# sensorX.net
KiCad netlist of a schematic drawn in EAGLE
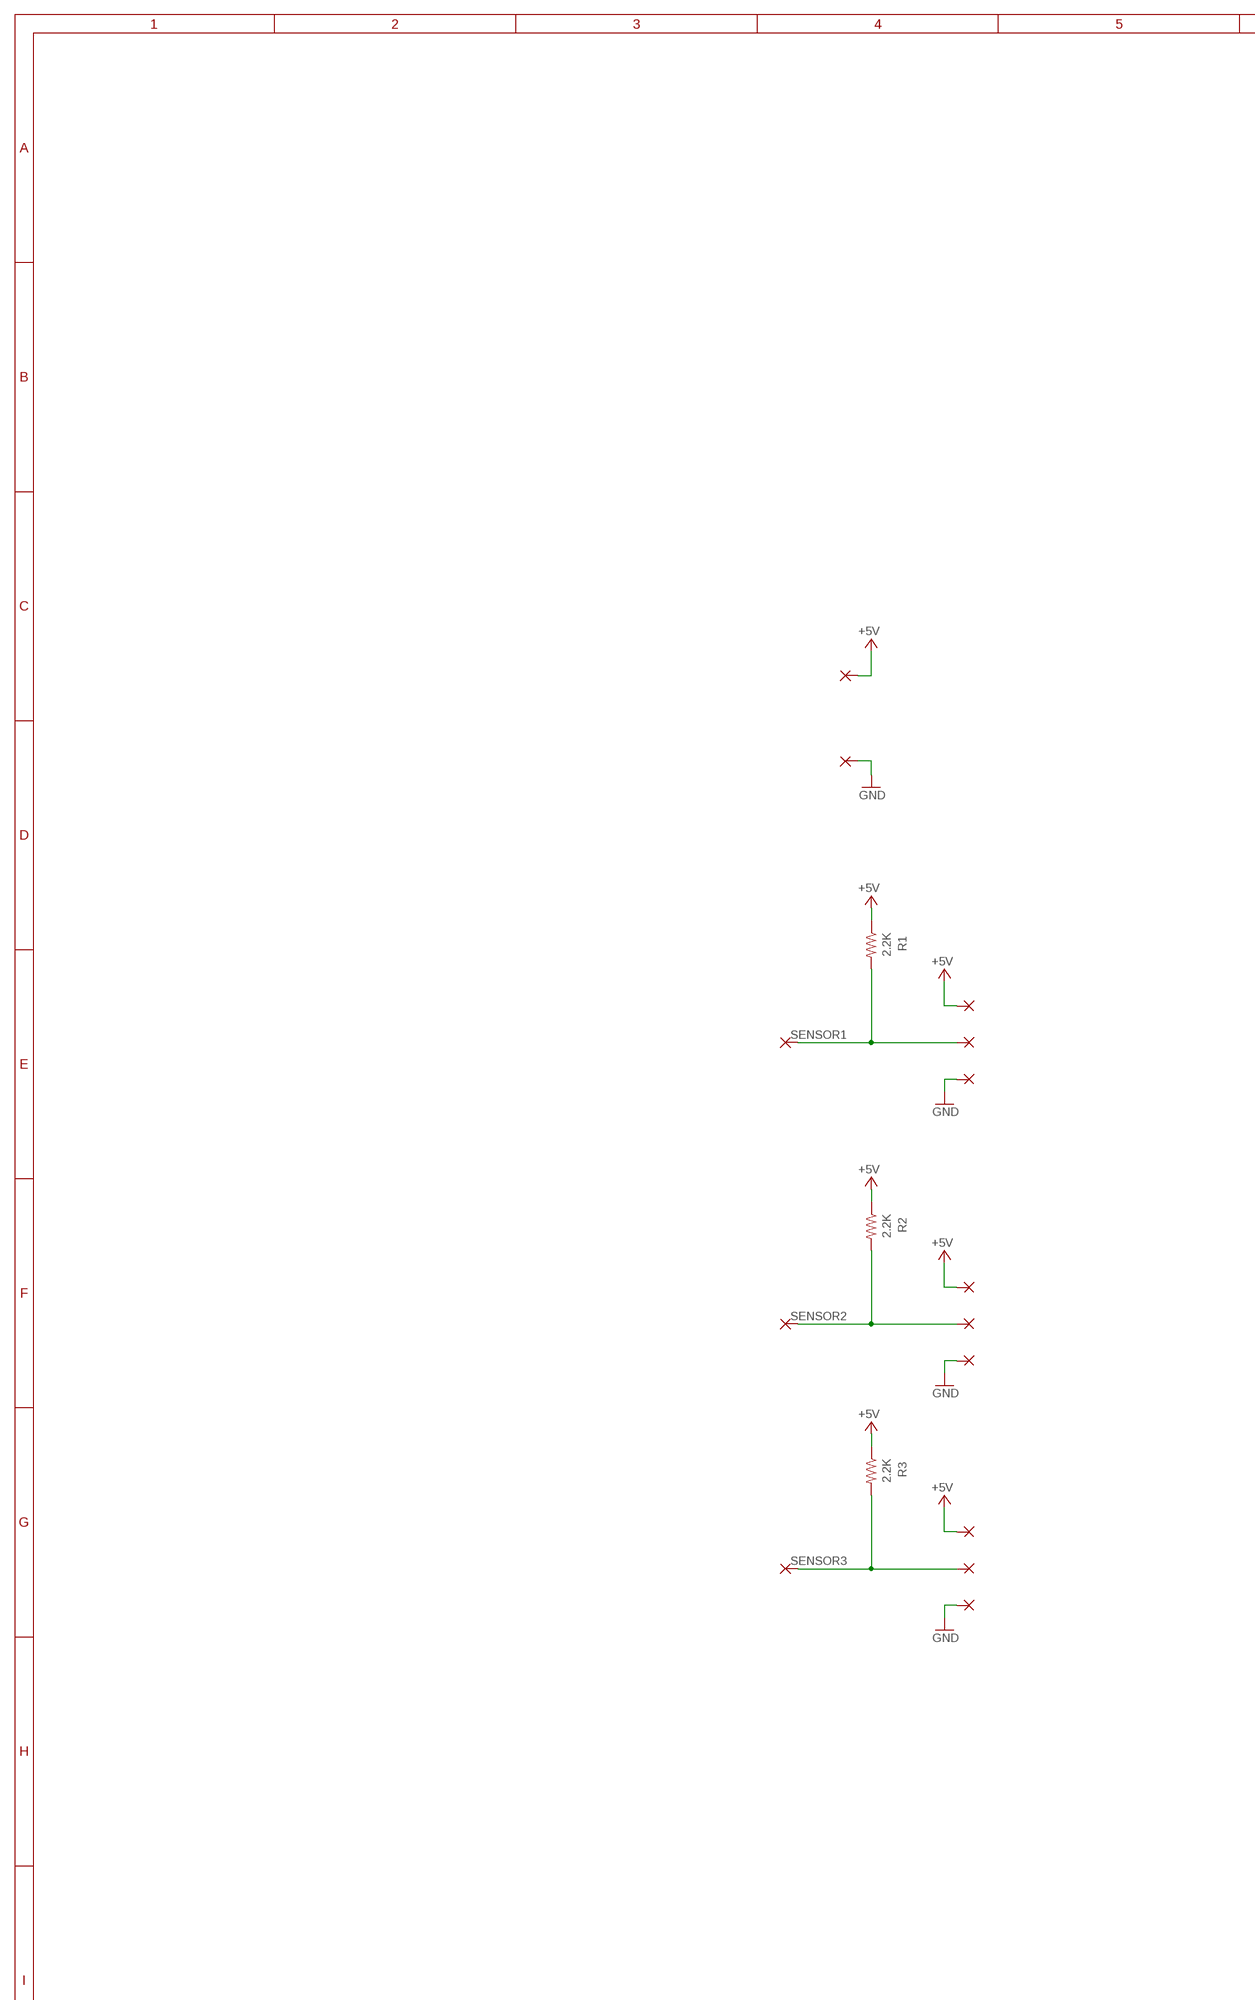
[diagram p0: schematic, sheet 1, part 1 of 2]
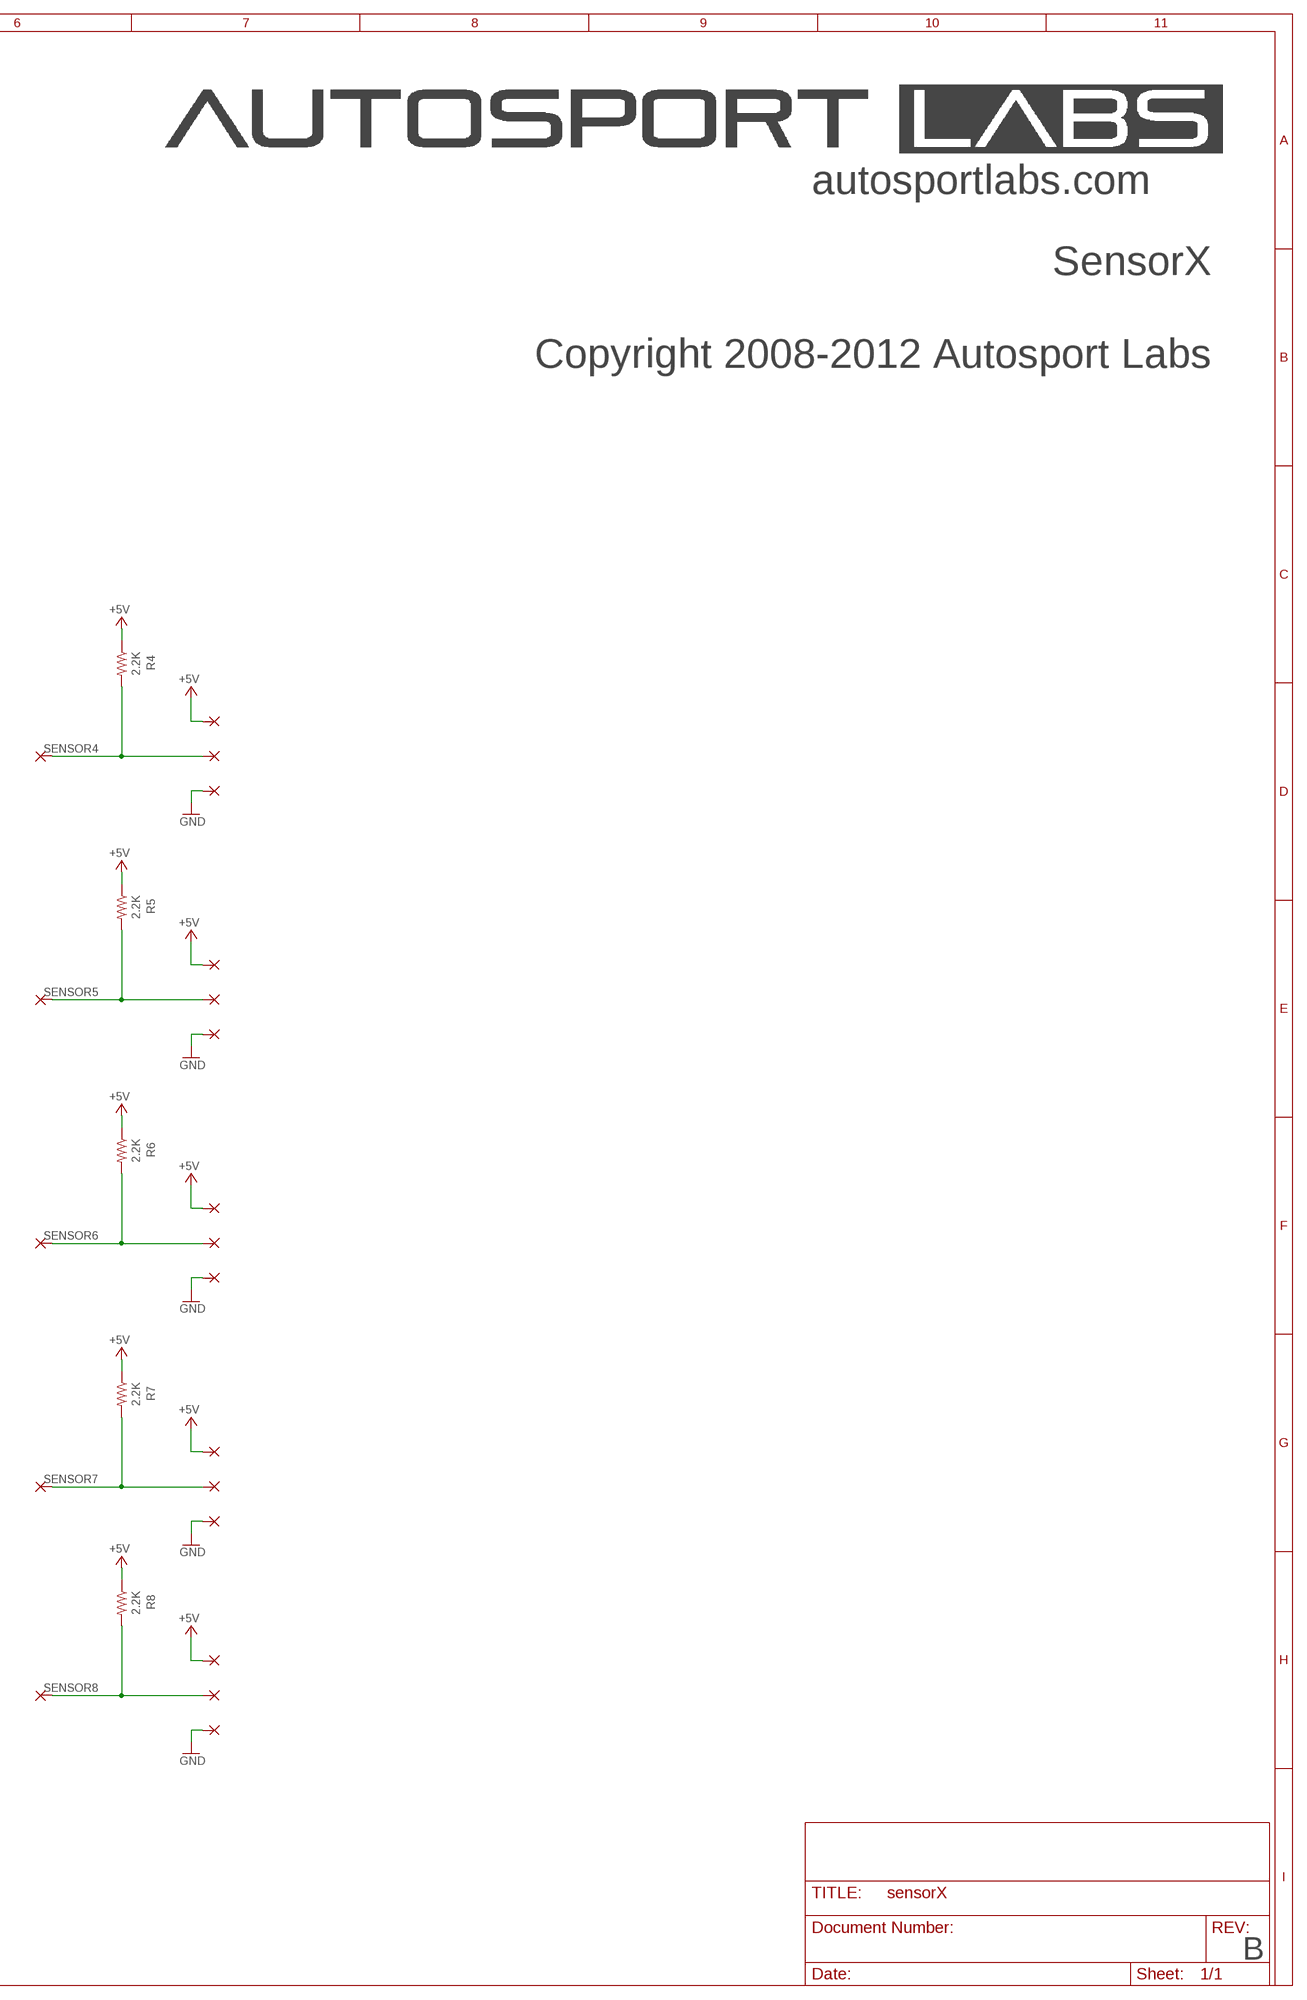
[diagram p1: schematic, sheet 1, part 2 of 2]

(export (version "E")
  (design (tool "Eeschema 10.0.6"))
  (components
    (comp (ref "1")
      (value "WIREPAD3,17/1,2")
      (footprint "eagle-import:3,17_1,2")
      (libsource (lib "eagle-import") (part "WIREPAD3,17/1,2"))
    )
    (comp (ref "2")
      (value "WIREPAD3,17/1,2")
      (footprint "eagle-import:3,17_1,2")
      (libsource (lib "eagle-import") (part "WIREPAD3,17/1,2"))
    )
    (comp (ref "3")
      (value "WIREPAD3,17/1,2")
      (footprint "eagle-import:3,17_1,2")
      (libsource (lib "eagle-import") (part "WIREPAD3,17/1,2"))
    )
    (comp (ref "4")
      (value "WIREPAD3,17/1,2")
      (footprint "eagle-import:3,17_1,2")
      (libsource (lib "eagle-import") (part "WIREPAD3,17/1,2"))
    )
    (comp (ref "5")
      (value "WIREPAD3,17/1,2")
      (footprint "eagle-import:3,17_1,2")
      (libsource (lib "eagle-import") (part "WIREPAD3,17/1,2"))
    )
    (comp (ref "5V")
      (value "WIREPAD3,17/1,2")
      (footprint "eagle-import:3,17_1,2")
      (libsource (lib "eagle-import") (part "WIREPAD3,17/1,2"))
    )
    (comp (ref "5V_1")
      (value "WIREPAD3,17/1,2")
      (footprint "eagle-import:3,17_1,2")
      (libsource (lib "eagle-import") (part "WIREPAD3,17/1,2"))
    )
    (comp (ref "5V_2")
      (value "WIREPAD3,17/1,2")
      (footprint "eagle-import:3,17_1,2")
      (libsource (lib "eagle-import") (part "WIREPAD3,17/1,2"))
    )
    (comp (ref "5V_3")
      (value "WIREPAD3,17/1,2")
      (footprint "eagle-import:3,17_1,2")
      (libsource (lib "eagle-import") (part "WIREPAD3,17/1,2"))
    )
    (comp (ref "5V_4")
      (value "WIREPAD3,17/1,2")
      (footprint "eagle-import:3,17_1,2")
      (libsource (lib "eagle-import") (part "WIREPAD3,17/1,2"))
    )
    (comp (ref "5V_5")
      (value "WIREPAD3,17/1,2")
      (footprint "eagle-import:3,17_1,2")
      (libsource (lib "eagle-import") (part "WIREPAD3,17/1,2"))
    )
    (comp (ref "5V_6")
      (value "WIREPAD3,17/1,2")
      (footprint "eagle-import:3,17_1,2")
      (libsource (lib "eagle-import") (part "WIREPAD3,17/1,2"))
    )
    (comp (ref "5V_7")
      (value "WIREPAD3,17/1,2")
      (footprint "eagle-import:3,17_1,2")
      (libsource (lib "eagle-import") (part "WIREPAD3,17/1,2"))
    )
    (comp (ref "5V_8")
      (value "WIREPAD3,17/1,2")
      (footprint "eagle-import:3,17_1,2")
      (libsource (lib "eagle-import") (part "WIREPAD3,17/1,2"))
    )
    (comp (ref "6")
      (value "WIREPAD3,17/1,2")
      (footprint "eagle-import:3,17_1,2")
      (libsource (lib "eagle-import") (part "WIREPAD3,17/1,2"))
    )
    (comp (ref "7")
      (value "WIREPAD3,17/1,2")
      (footprint "eagle-import:3,17_1,2")
      (libsource (lib "eagle-import") (part "WIREPAD3,17/1,2"))
    )
    (comp (ref "7_IN")
      (value "WIREPAD3,17/1,2")
      (footprint "eagle-import:3,17_1,2")
      (libsource (lib "eagle-import") (part "WIREPAD3,17/1,2"))
    )
    (comp (ref "8")
      (value "WIREPAD3,17/1,2")
      (footprint "eagle-import:3,17_1,2")
      (libsource (lib "eagle-import") (part "WIREPAD3,17/1,2"))
    )
    (comp (ref "8_IN")
      (value "WIREPAD3,17/1,2")
      (footprint "eagle-import:3,17_1,2")
      (libsource (lib "eagle-import") (part "WIREPAD3,17/1,2"))
    )
    (comp (ref "GND")
      (value "WIREPAD3,17/1,2")
      (footprint "eagle-import:3,17_1,2")
      (libsource (lib "eagle-import") (part "WIREPAD3,17/1,2"))
    )
    (comp (ref "GND-1")
      (value "WIREPAD3,17/1,2")
      (footprint "eagle-import:3,17_1,2")
      (libsource (lib "eagle-import") (part "WIREPAD3,17/1,2"))
    )
    (comp (ref "GND_2")
      (value "WIREPAD3,17/1,2")
      (footprint "eagle-import:3,17_1,2")
      (libsource (lib "eagle-import") (part "WIREPAD3,17/1,2"))
    )
    (comp (ref "GND_3")
      (value "WIREPAD3,17/1,2")
      (footprint "eagle-import:3,17_1,2")
      (libsource (lib "eagle-import") (part "WIREPAD3,17/1,2"))
    )
    (comp (ref "GND_4")
      (value "WIREPAD3,17/1,2")
      (footprint "eagle-import:3,17_1,2")
      (libsource (lib "eagle-import") (part "WIREPAD3,17/1,2"))
    )
    (comp (ref "GND_5")
      (value "WIREPAD3,17/1,2")
      (footprint "eagle-import:3,17_1,2")
      (libsource (lib "eagle-import") (part "WIREPAD3,17/1,2"))
    )
    (comp (ref "GND_6")
      (value "WIREPAD3,17/1,2")
      (footprint "eagle-import:3,17_1,2")
      (libsource (lib "eagle-import") (part "WIREPAD3,17/1,2"))
    )
    (comp (ref "GND_7")
      (value "WIREPAD3,17/1,2")
      (footprint "eagle-import:3,17_1,2")
      (libsource (lib "eagle-import") (part "WIREPAD3,17/1,2"))
    )
    (comp (ref "GND_8")
      (value "WIREPAD3,17/1,2")
      (footprint "eagle-import:3,17_1,2")
      (libsource (lib "eagle-import") (part "WIREPAD3,17/1,2"))
    )
    (comp (ref "IN_1")
      (value "WIREPAD3,17/1,2")
      (footprint "eagle-import:3,17_1,2")
      (libsource (lib "eagle-import") (part "WIREPAD3,17/1,2"))
    )
    (comp (ref "IN_2")
      (value "WIREPAD3,17/1,2")
      (footprint "eagle-import:3,17_1,2")
      (libsource (lib "eagle-import") (part "WIREPAD3,17/1,2"))
    )
    (comp (ref "IN_3")
      (value "WIREPAD3,17/1,2")
      (footprint "eagle-import:3,17_1,2")
      (libsource (lib "eagle-import") (part "WIREPAD3,17/1,2"))
    )
    (comp (ref "IN_4")
      (value "WIREPAD3,17/1,2")
      (footprint "eagle-import:3,17_1,2")
      (libsource (lib "eagle-import") (part "WIREPAD3,17/1,2"))
    )
    (comp (ref "IN_5")
      (value "WIREPAD3,17/1,2")
      (footprint "eagle-import:3,17_1,2")
      (libsource (lib "eagle-import") (part "WIREPAD3,17/1,2"))
    )
    (comp (ref "IN_6")
      (value "WIREPAD3,17/1,2")
      (footprint "eagle-import:3,17_1,2")
      (libsource (lib "eagle-import") (part "WIREPAD3,17/1,2"))
    )
    (comp (ref "R1")
      (value "2.2K")
      (footprint "eagle-import:0204_5")
      (libsource (lib "eagle-import") (part "R-US_0204/5"))
    )
    (comp (ref "R2")
      (value "2.2K")
      (footprint "eagle-import:0204_5")
      (libsource (lib "eagle-import") (part "R-US_0204/5"))
    )
    (comp (ref "R3")
      (value "2.2K")
      (footprint "eagle-import:0204_5")
      (libsource (lib "eagle-import") (part "R-US_0204/5"))
    )
    (comp (ref "R4")
      (value "2.2K")
      (footprint "eagle-import:0204_5")
      (libsource (lib "eagle-import") (part "R-US_0204/5"))
    )
    (comp (ref "R5")
      (value "2.2K")
      (footprint "eagle-import:0204_5")
      (libsource (lib "eagle-import") (part "R-US_0204/5"))
    )
    (comp (ref "R6")
      (value "2.2K")
      (footprint "eagle-import:0204_5")
      (libsource (lib "eagle-import") (part "R-US_0204/5"))
    )
    (comp (ref "R7")
      (value "2.2K")
      (footprint "eagle-import:0204_5")
      (libsource (lib "eagle-import") (part "R-US_0204/5"))
    )
    (comp (ref "R8")
      (value "2.2K")
      (footprint "eagle-import:0204_5")
      (libsource (lib "eagle-import") (part "R-US_0204/5"))
    )
  )
  (nets
    (net (code "1") (name "+5V") (class "Default")
      (node (ref "5V") (pin "1") (pinfunction "P_1") (pintype "passive"))
      (node (ref "5V_1") (pin "1") (pinfunction "P_1") (pintype "passive"))
      (node (ref "5V_2") (pin "1") (pinfunction "P_1") (pintype "passive"))
      (node (ref "5V_3") (pin "1") (pinfunction "P_1") (pintype "passive"))
      (node (ref "5V_4") (pin "1") (pinfunction "P_1") (pintype "passive"))
      (node (ref "5V_5") (pin "1") (pinfunction "P_1") (pintype "passive"))
      (node (ref "5V_6") (pin "1") (pinfunction "P_1") (pintype "passive"))
      (node (ref "5V_7") (pin "1") (pinfunction "P_1") (pintype "passive"))
      (node (ref "5V_8") (pin "1") (pinfunction "P_1") (pintype "passive"))
      (node (ref "R1") (pin "1") (pinfunction "1_1") (pintype "passive"))
      (node (ref "R2") (pin "1") (pinfunction "1_1") (pintype "passive"))
      (node (ref "R3") (pin "1") (pinfunction "1_1") (pintype "passive"))
      (node (ref "R4") (pin "1") (pinfunction "1_1") (pintype "passive"))
      (node (ref "R5") (pin "1") (pinfunction "1_1") (pintype "passive"))
      (node (ref "R6") (pin "1") (pinfunction "1_1") (pintype "passive"))
      (node (ref "R7") (pin "1") (pinfunction "1_1") (pintype "passive"))
      (node (ref "R8") (pin "1") (pinfunction "1_1") (pintype "passive"))
    )
    (net (code "2") (name "/SENSOR1") (class "Default")
      (node (ref "1") (pin "1") (pinfunction "P_1") (pintype "passive"))
      (node (ref "IN_1") (pin "1") (pinfunction "P_1") (pintype "passive"))
      (node (ref "R1") (pin "2") (pinfunction "2_2") (pintype "passive"))
    )
    (net (code "3") (name "/SENSOR2") (class "Default")
      (node (ref "2") (pin "1") (pinfunction "P_1") (pintype "passive"))
      (node (ref "IN_2") (pin "1") (pinfunction "P_1") (pintype "passive"))
      (node (ref "R2") (pin "2") (pinfunction "2_2") (pintype "passive"))
    )
    (net (code "4") (name "/SENSOR3") (class "Default")
      (node (ref "3") (pin "1") (pinfunction "P_1") (pintype "passive"))
      (node (ref "IN_3") (pin "1") (pinfunction "P_1") (pintype "passive"))
      (node (ref "R3") (pin "2") (pinfunction "2_2") (pintype "passive"))
    )
    (net (code "5") (name "/SENSOR4") (class "Default")
      (node (ref "4") (pin "1") (pinfunction "P_1") (pintype "passive"))
      (node (ref "IN_4") (pin "1") (pinfunction "P_1") (pintype "passive"))
      (node (ref "R4") (pin "2") (pinfunction "2_2") (pintype "passive"))
    )
    (net (code "6") (name "/SENSOR5") (class "Default")
      (node (ref "5") (pin "1") (pinfunction "P_1") (pintype "passive"))
      (node (ref "IN_5") (pin "1") (pinfunction "P_1") (pintype "passive"))
      (node (ref "R5") (pin "2") (pinfunction "2_2") (pintype "passive"))
    )
    (net (code "7") (name "/SENSOR6") (class "Default")
      (node (ref "6") (pin "1") (pinfunction "P_1") (pintype "passive"))
      (node (ref "IN_6") (pin "1") (pinfunction "P_1") (pintype "passive"))
      (node (ref "R6") (pin "2") (pinfunction "2_2") (pintype "passive"))
    )
    (net (code "8") (name "/SENSOR7") (class "Default")
      (node (ref "7") (pin "1") (pinfunction "P_1") (pintype "passive"))
      (node (ref "7_IN") (pin "1") (pinfunction "P_1") (pintype "passive"))
      (node (ref "R7") (pin "2") (pinfunction "2_2") (pintype "passive"))
    )
    (net (code "9") (name "/SENSOR8") (class "Default")
      (node (ref "8") (pin "1") (pinfunction "P_1") (pintype "passive"))
      (node (ref "8_IN") (pin "1") (pinfunction "P_1") (pintype "passive"))
      (node (ref "R8") (pin "2") (pinfunction "2_2") (pintype "passive"))
    )
    (net (code "10") (name "GND") (class "Default")
      (node (ref "GND") (pin "1") (pinfunction "P_1") (pintype "passive"))
      (node (ref "GND-1") (pin "1") (pinfunction "P_1") (pintype "passive"))
      (node (ref "GND_2") (pin "1") (pinfunction "P_1") (pintype "passive"))
      (node (ref "GND_3") (pin "1") (pinfunction "P_1") (pintype "passive"))
      (node (ref "GND_4") (pin "1") (pinfunction "P_1") (pintype "passive"))
      (node (ref "GND_5") (pin "1") (pinfunction "P_1") (pintype "passive"))
      (node (ref "GND_6") (pin "1") (pinfunction "P_1") (pintype "passive"))
      (node (ref "GND_7") (pin "1") (pinfunction "P_1") (pintype "passive"))
      (node (ref "GND_8") (pin "1") (pinfunction "P_1") (pintype "passive"))
    )
  )
)
